# DIOT_Connectors.net
KiCad netlist of a schematic drawn in Altium Designer
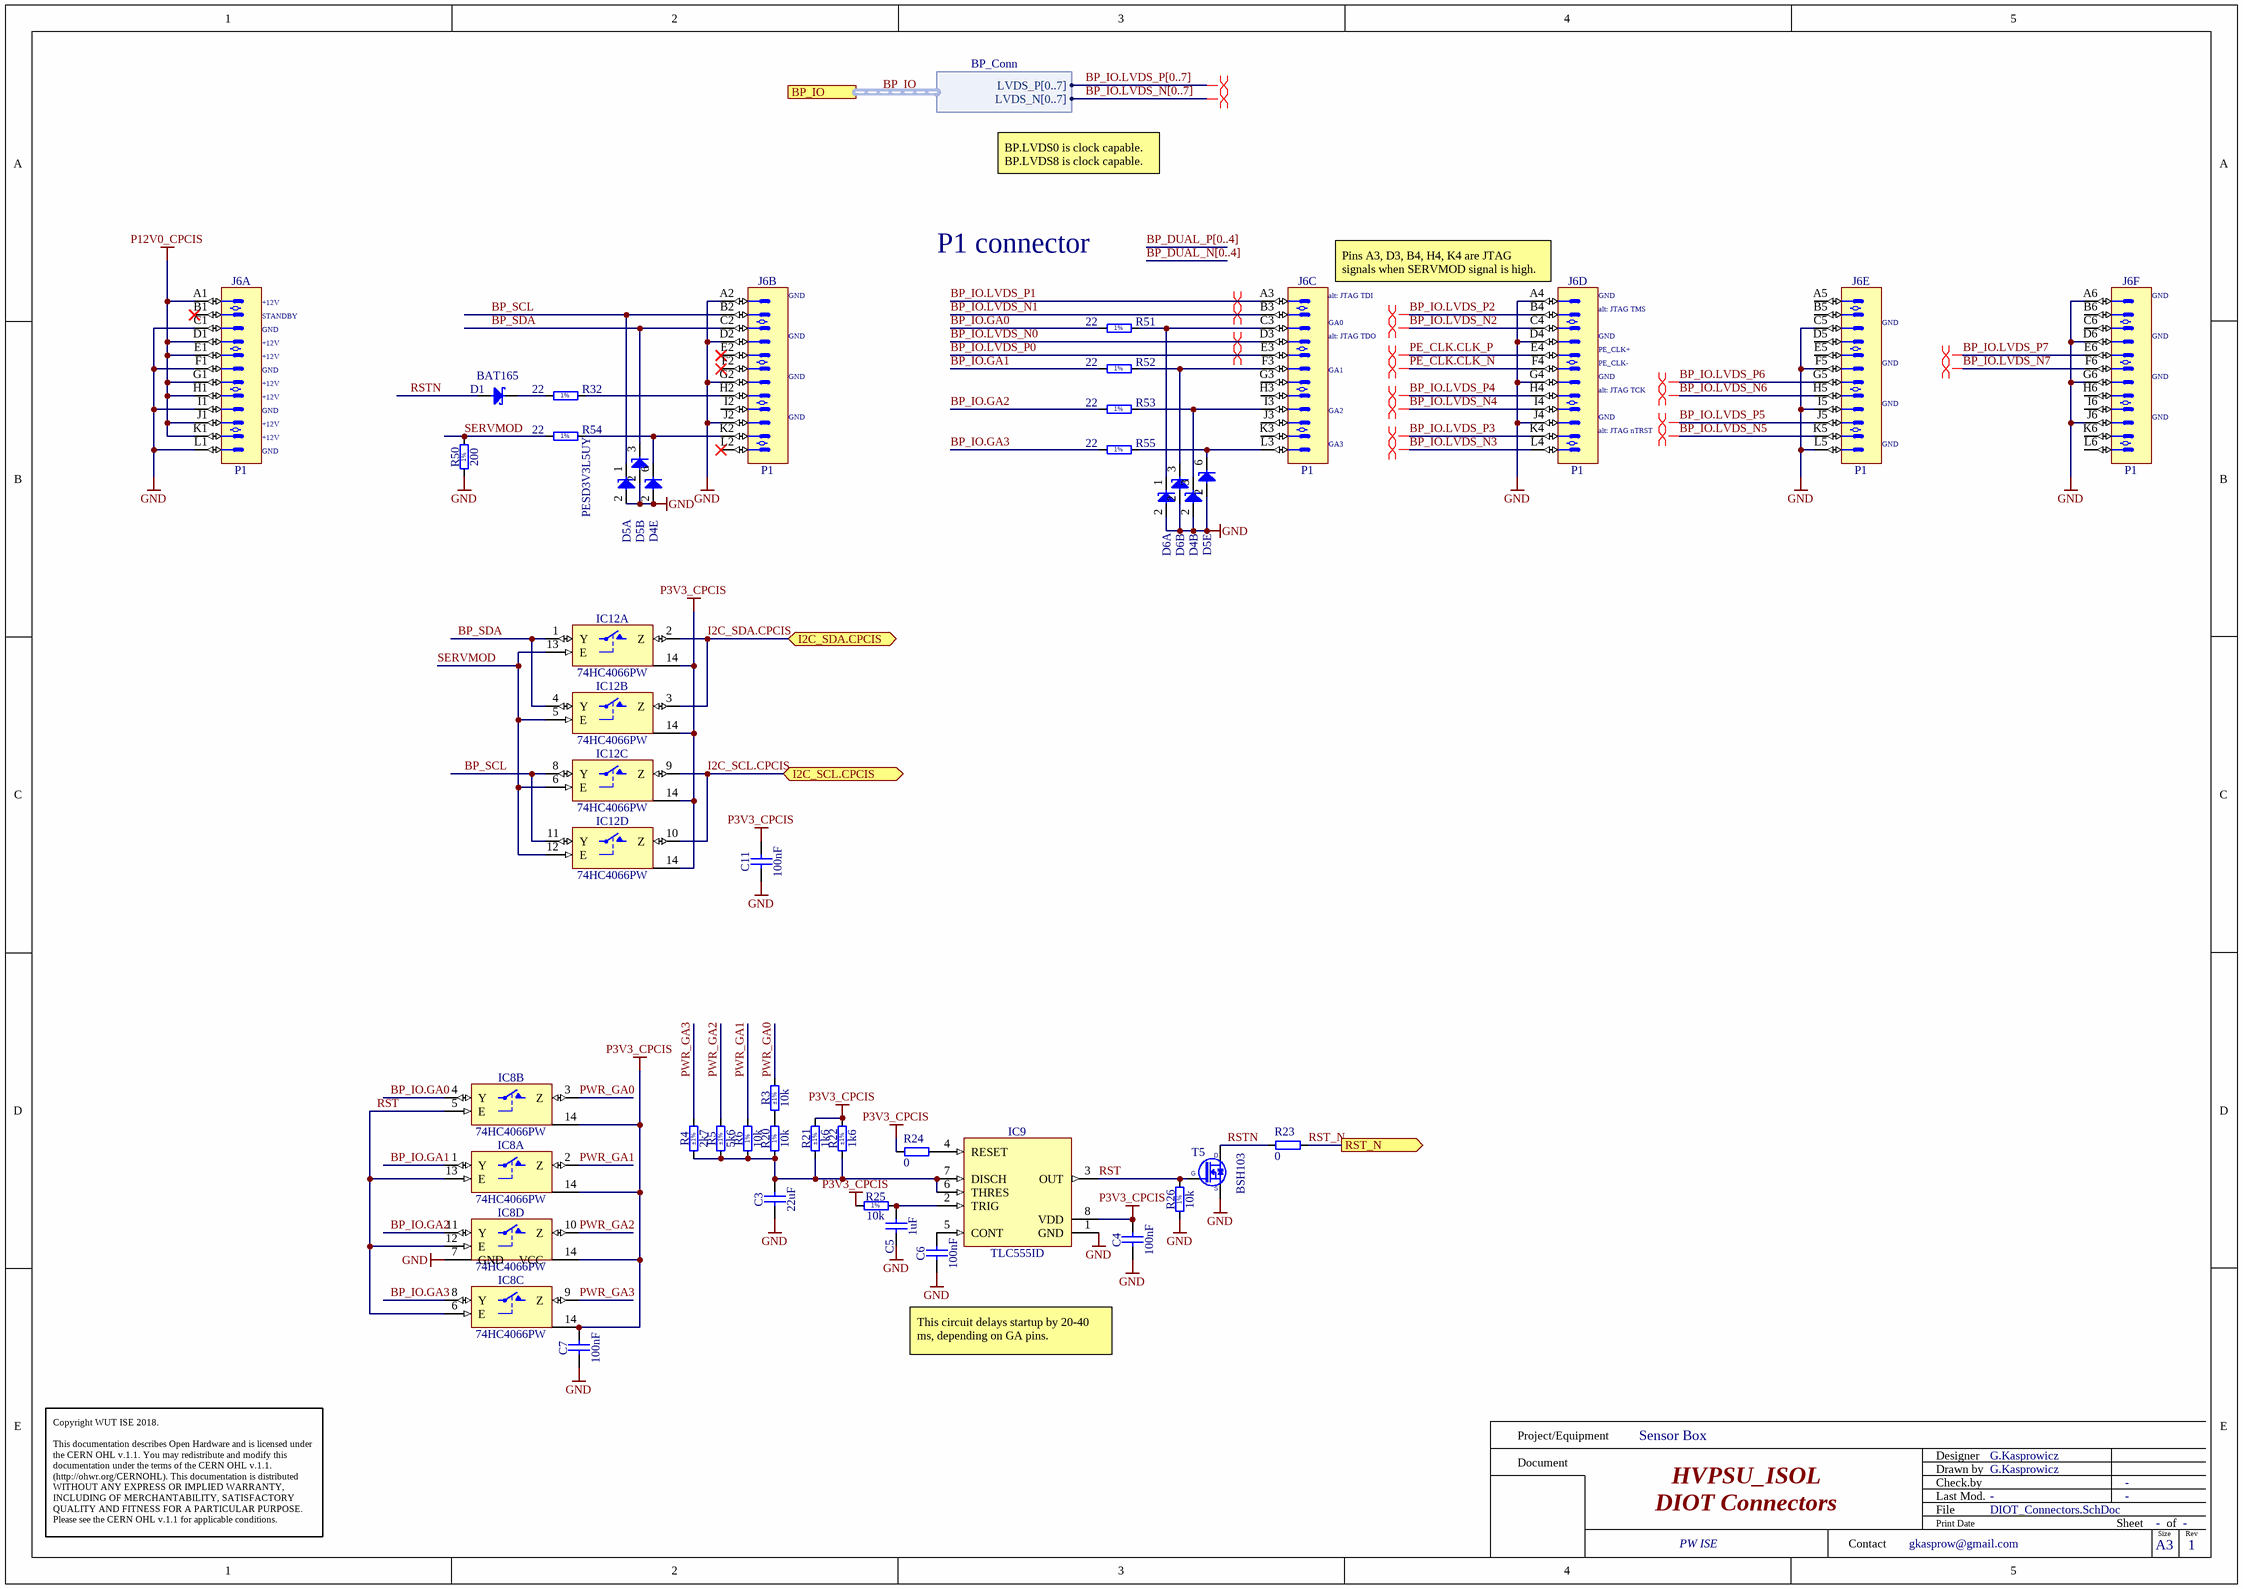
[diagram p0: DIOT_Connectors.SchDoc]

(export (version "E")
  (design (tool "Eeschema 10.0.6"))
  (components
    (comp (ref "C3")
      (value "22uF")
      (footprint "CAPC1608X90N")
      (description "Non-polarised capacitor")
      (fields
        (field (name "MANUFACTURER") "GENERIC")
        (field (name "PART NUMBER") "CC0603_22UF_6.3V_20%_X5R")
        (field (name "AUTHOR") "CERN DEM JLC")
      )
      (libsource (lib "Capacitors") (part "Capacitor - non polarized"))
    )
    (comp (ref "C4")
      (value "100nF")
      (footprint "CAPC1005X55N")
      (description "Non-polarised capacitor")
      (fields
        (field (name "PART NUMBER") "CC0402_100NF_16V_10%_X5R")
        (field (name "VOLTAGE") "16V")
        (field (name "AUTHOR") "CERN DEM JLC")
      )
      (libsource (lib "Capacitors") (part "Capacitor - non polarized"))
    )
    (comp (ref "C5")
      (value "1uF")
      (footprint "CAPC1005X55N")
      (description "Non-polarised capacitor")
      (fields
        (field (name "PART NUMBER") "CC0402_1UF_16V_10%_X5R")
        (field (name "VOLTAGE") "16V")
        (field (name "AUTHOR") "CERN DEM JLC")
      )
      (libsource (lib "Capacitors") (part "Capacitor - non polarized"))
    )
    (comp (ref "C6")
      (value "100nF")
      (footprint "CAPC1005X55N")
      (description "Non-polarised capacitor")
      (fields
        (field (name "PART NUMBER") "CC0402_100NF_16V_10%_X5R")
        (field (name "VOLTAGE") "16V")
        (field (name "AUTHOR") "CERN DEM JLC")
      )
      (libsource (lib "Capacitors") (part "Capacitor - non polarized"))
    )
    (comp (ref "C7")
      (value "100nF")
      (footprint "CAPC1005X55N")
      (description "Non-polarised capacitor")
      (fields
        (field (name "PART NUMBER") "CC0402_100NF_16V_10%_X5R")
        (field (name "VOLTAGE") "16V")
        (field (name "AUTHOR") "CERN DEM JLC")
      )
      (libsource (lib "Capacitors") (part "Capacitor - non polarized"))
    )
    (comp (ref "C11")
      (value "100nF")
      (footprint "CAPC1005X55N")
      (description "Non-polarised capacitor")
      (fields
        (field (name "PART NUMBER") "CC0402_100NF_16V_10%_X5R")
        (field (name "VOLTAGE") "16V")
        (field (name "AUTHOR") "CERN DEM JLC")
      )
      (libsource (lib "Capacitors") (part "Capacitor - non polarized"))
    )
    (comp (ref "D1")
      (value "BAT165")
      (footprint "SOD2512X110N")
      (description "Schottky Diode")
      (fields
        (field (name "MANUFACTURER") "INFINEON")
        (field (name "VOLTAGE") "40V")
        (field (name "AUTHOR") "CERN DEM JLC")
      )
      (libsource (lib "ICs And Semiconductors") (part "Diode Schottky"))
    )
    (comp (ref "D4")
      (value "PESD3V3L5UY")
      (footprint "SOT65P210X110-6N")
      (description "Fivefold ESD Protection Diode Arrays")
      (fields
        (field (name "VOLTAGE") "3.3V")
        (field (name "POWER") "200W")
        (field (name "AUTHOR") "CERN DEM WB")
      )
      (libsource (lib "ICs And Semiconductors") (part "PESD Array 5diodes 6pins Common anode2"))
    )
    (comp (ref "D5")
      (value "PESD3V3L5UY")
      (footprint "SOT65P210X110-6N")
      (description "Fivefold ESD Protection Diode Arrays")
      (fields
        (field (name "VOLTAGE") "3.3V")
        (field (name "POWER") "200W")
        (field (name "AUTHOR") "CERN DEM WB")
      )
      (libsource (lib "ICs And Semiconductors") (part "PESD Array 5diodes 6pins Common anode2"))
    )
    (comp (ref "D6")
      (value "PESD3V3L5UY")
      (footprint "SOT65P210X110-6N")
      (description "Fivefold ESD Protection Diode Arrays")
      (fields
        (field (name "VOLTAGE") "3.3V")
        (field (name "POWER") "200W")
        (field (name "AUTHOR") "CERN DEM WB")
      )
      (libsource (lib "ICs And Semiconductors") (part "PESD Array 5diodes 6pins Common anode2"))
    )
    (comp (ref "IC8")
      (value "74HC4066PW")
      (footprint "SOP65P640X110-14N")
      (fields (field (name "MANUFACTURER") "NXP SEMICONDUCTORS") (field (name "AUTHOR") "CERN DEM JLC"))
      (libsource (lib "ICs And Semiconductors") (part "4066"))
    )
    (comp (ref "IC9")
      (value "TLC555ID")
      (footprint "SOIC127P600X175-8N")
      (description "LinCMOS Timer")
      (fields (field (name "MANUFACTURER") "TEXAS INSTRUMENTS") (field (name "AUTHOR") "CERN DEM JMW"))
      (libsource (lib "ICs And Semiconductors") (part "TLC555"))
    )
    (comp (ref "IC12")
      (value "74HC4066PW")
      (footprint "SOP65P640X110-14N")
      (fields (field (name "MANUFACTURER") "NXP SEMICONDUCTORS") (field (name "AUTHOR") "CERN DEM JLC"))
      (libsource (lib "ICs And Semiconductors") (part "4066"))
    )
    (comp (ref "J6")
      (value "P1")
      (footprint "AMPHENOL_10052825-101LF")
      (description "72 Contacts Header, 6 Columns, 4 Pairs per Column")
      (fields
        (field (name "PART NUMBER") "AMPHENOL_10052825-101LF")
        (field (name "MANUFACTURER") "AMPHENOL")
        (field (name "AUTHOR") "CERN DEM MR")
      )
      (libsource (lib "Connectors") (part "AMPHENOL_10052825-101LF"))
    )
    (comp (ref "R3")
      (value "10k")
      (footprint "RESC1005X40N")
      (description "Resistor - 1%")
      (fields
        (field (name "PART NUMBER") "R0402_10K_1%_0.0625W_100PPM")
        (field (name "POWER") "0.0625W")
        (field (name "TOLERANCE") "±1%")
        (field (name "AUTHOR") "CERN DEM JLC")
      )
      (libsource (lib "Resistors") (part "Resistor - 1%"))
    )
    (comp (ref "R4")
      (value "2k7")
      (footprint "RESC1608X55N")
      (description "Resistor - 1%")
      (fields
        (field (name "PART NUMBER") "R0603_2K7_1%_0.1W_100PPM")
        (field (name "POWER") "0.1W")
        (field (name "TOLERANCE") "±1%")
        (field (name "AUTHOR") "CERN DEM JLC")
      )
      (libsource (lib "") (part "Resistor - 1%_1"))
    )
    (comp (ref "R5")
      (value "5k6")
      (footprint "RESC1005X40N")
      (description "Resistor - 1%")
      (fields
        (field (name "PART NUMBER") "R0402_5K6_1%_0.0625W_100PPM")
        (field (name "POWER") "0.0625W")
        (field (name "TOLERANCE") "±1%")
        (field (name "AUTHOR") "CERN DEM JLC")
      )
      (libsource (lib "Resistors") (part "Resistor - 1%"))
    )
    (comp (ref "R6")
      (value "10k")
      (footprint "RESC1005X40N")
      (description "Resistor - 1%")
      (fields
        (field (name "PART NUMBER") "R0402_1K_1%_0.0625W_100PPM")
        (field (name "POWER") "0.0625W")
        (field (name "AUTHOR") "CERN DEM JLC")
      )
      (libsource (lib "Resistors") (part "Resistor - 1%"))
    )
    (comp (ref "R20")
      (value "10k")
      (footprint "RESC1005X40N")
      (description "Resistor - 1%")
      (fields
        (field (name "PART NUMBER") "R0402_1K_1%_0.0625W_100PPM")
        (field (name "POWER") "0.0625W")
        (field (name "AUTHOR") "CERN DEM JLC")
      )
      (libsource (lib "Resistors") (part "Resistor - 1%"))
    )
    (comp (ref "R21")
      (value "1k6")
      (footprint "RESC1005X40N")
      (description "Resistor - 1%")
      (fields
        (field (name "PART NUMBER") "R0402_1K6_1%_0.0625W_100PPM")
        (field (name "POWER") "0.0625W")
        (field (name "TOLERANCE") "±1%")
        (field (name "AUTHOR") "CERN DEM JLC")
      )
      (libsource (lib "Resistors") (part "Resistor - 1%"))
    )
    (comp (ref "R22")
      (value "1k6")
      (footprint "RESC1005X40N")
      (description "Resistor - 1%")
      (fields
        (field (name "PART NUMBER") "R0402_1K6_1%_0.0625W_100PPM")
        (field (name "POWER") "0.0625W")
        (field (name "TOLERANCE") "±1%")
        (field (name "AUTHOR") "CERN DEM JLC")
      )
      (libsource (lib "Resistors") (part "Resistor - 1%"))
    )
    (comp (ref "R23")
      (value "0")
      (footprint "RESC1005X40N")
      (description "Resistor")
      (fields
        (field (name "PART NUMBER") "R0402_0R_JUMPER")
        (field (name "MANUFACTURER") "GENERIC")
        (field (name "AUTHOR") "CERN DEM JLC")
      )
      (libsource (lib "Resistors") (part "Resistor"))
    )
    (comp (ref "R24")
      (value "0")
      (footprint "RESC1005X40N")
      (description "Resistor")
      (fields
        (field (name "PART NUMBER") "R0402_0R_JUMPER")
        (field (name "MANUFACTURER") "GENERIC")
        (field (name "AUTHOR") "CERN DEM JLC")
      )
      (libsource (lib "Resistors") (part "Resistor"))
    )
    (comp (ref "R25")
      (value "10k")
      (footprint "RESC1005X40N")
      (description "Resistor - 1%")
      (fields
        (field (name "PART NUMBER") "R0402_10K_1%_0.0625W_100PPM")
        (field (name "POWER") "0.0625W")
        (field (name "AUTHOR") "CERN DEM JLC")
      )
      (libsource (lib "Resistors") (part "Resistor - 1%"))
    )
    (comp (ref "R26")
      (value "10k")
      (footprint "RESC1005X40N")
      (description "Resistor - 1%")
      (fields
        (field (name "PART NUMBER") "R0402_10K_1%_0.0625W_100PPM")
        (field (name "POWER") "0.0625W")
        (field (name "AUTHOR") "CERN DEM JLC")
      )
      (libsource (lib "Resistors") (part "Resistor - 1%"))
    )
    (comp (ref "R32")
      (value "22")
      (footprint "RESC1005X40N")
      (description "Resistor - 1%")
      (fields
        (field (name "PART NUMBER") "R0402_22R_1%_0.0625W_100PPM")
        (field (name "POWER") "0.0625W")
        (field (name "AUTHOR") "CERN DEM JLC")
      )
      (libsource (lib "Resistors") (part "Resistor - 1%"))
    )
    (comp (ref "R50")
      (value "200")
      (footprint "RESC1005X40N")
      (description "Resistor - 1%")
      (fields
        (field (name "PART NUMBER") "R0402_200R_1%_0.0625W_100PPM")
        (field (name "POWER") "0.0625W")
        (field (name "AUTHOR") "CERN DEM JLC")
      )
      (libsource (lib "Resistors") (part "Resistor - 1%"))
    )
    (comp (ref "R51")
      (value "22")
      (footprint "RESC1005X40N")
      (description "Resistor - 1%")
      (fields
        (field (name "PART NUMBER") "R0402_22R_1%_0.0625W_100PPM")
        (field (name "POWER") "0.0625W")
        (field (name "AUTHOR") "CERN DEM JLC")
      )
      (libsource (lib "Resistors") (part "Resistor - 1%"))
    )
    (comp (ref "R52")
      (value "22")
      (footprint "RESC1005X40N")
      (description "Resistor - 1%")
      (fields
        (field (name "PART NUMBER") "R0402_22R_1%_0.0625W_100PPM")
        (field (name "POWER") "0.0625W")
        (field (name "AUTHOR") "CERN DEM JLC")
      )
      (libsource (lib "Resistors") (part "Resistor - 1%"))
    )
    (comp (ref "R53")
      (value "22")
      (footprint "RESC1005X40N")
      (description "Resistor - 1%")
      (fields
        (field (name "PART NUMBER") "R0402_22R_1%_0.0625W_100PPM")
        (field (name "POWER") "0.0625W")
        (field (name "AUTHOR") "CERN DEM JLC")
      )
      (libsource (lib "Resistors") (part "Resistor - 1%"))
    )
    (comp (ref "R54")
      (value "22")
      (footprint "RESC1005X40N")
      (description "Resistor - 1%")
      (fields
        (field (name "PART NUMBER") "R0402_22R_1%_0.0625W_100PPM")
        (field (name "POWER") "0.0625W")
        (field (name "AUTHOR") "CERN DEM JLC")
      )
      (libsource (lib "Resistors") (part "Resistor - 1%"))
    )
    (comp (ref "R55")
      (value "22")
      (footprint "RESC1005X40N")
      (description "Resistor - 1%")
      (fields
        (field (name "PART NUMBER") "R0402_22R_1%_0.0625W_100PPM")
        (field (name "POWER") "0.0625W")
        (field (name "AUTHOR") "CERN DEM JLC")
      )
      (libsource (lib "Resistors") (part "Resistor - 1%"))
    )
    (comp (ref "T5")
      (value "BSH103")
      (footprint "SOT95P230X110-3N")
      (description "N-CHANNEL MOSFET WITH DIODE")
      (fields (field (name "MANUFACTURER") "NEXPERIA") (field (name "AUTHOR") "CERN DEM JLC"))
      (libsource (lib "ICs And Semiconductors") (part "N-MOSFET-D 1G 2S 3D"))
    )
  )
  (nets
    (net (code "14") (name "/BP_IO.GA0") (class "Default")
      (node (ref "IC8") (pin "4") (pinfunction "Y_4") (pintype "bidirectional"))
      (node (ref "R51") (pin "1") (pinfunction "1_1") (pintype "passive"))
    )
    (net (code "15") (name "/BP_IO.GA1") (class "Default")
      (node (ref "IC8") (pin "1") (pinfunction "Y_1") (pintype "bidirectional"))
      (node (ref "R52") (pin "1") (pinfunction "1_1") (pintype "passive"))
    )
    (net (code "16") (name "/BP_IO.GA2") (class "Default")
      (node (ref "IC8") (pin "11") (pinfunction "Y_11") (pintype "bidirectional"))
      (node (ref "R53") (pin "1") (pinfunction "1_1") (pintype "passive"))
    )
    (net (code "17") (name "/BP_IO.GA3") (class "Default")
      (node (ref "IC8") (pin "8") (pinfunction "Y_8") (pintype "bidirectional"))
      (node (ref "R55") (pin "1") (pinfunction "1_1") (pintype "passive"))
    )
    (net (code "18") (name "/BP_IO.LVDS_N0") (class "Default")
      (node (ref "J6") (pin "D3") (pinfunction "D3_D3") (pintype "bidirectional"))
    )
    (net (code "19") (name "/BP_IO.LVDS_N1") (class "Default")
      (node (ref "J6") (pin "B3") (pinfunction "B3_B3") (pintype "bidirectional"))
    )
    (net (code "20") (name "/BP_IO.LVDS_N2") (class "Default")
      (node (ref "J6") (pin "C4") (pinfunction "C4_C4") (pintype "bidirectional"))
    )
    (net (code "21") (name "/BP_IO.LVDS_N3") (class "Default")
      (node (ref "J6") (pin "L4") (pinfunction "L4_L4") (pintype "bidirectional"))
    )
    (net (code "22") (name "/BP_IO.LVDS_N4") (class "Default")
      (node (ref "J6") (pin "I4") (pinfunction "I4_I4") (pintype "bidirectional"))
    )
    (net (code "23") (name "/BP_IO.LVDS_N5") (class "Default")
      (node (ref "J6") (pin "K5") (pinfunction "K5_K5") (pintype "bidirectional"))
    )
    (net (code "24") (name "/BP_IO.LVDS_N6") (class "Default")
      (node (ref "J6") (pin "H5") (pinfunction "H5_H5") (pintype "bidirectional"))
    )
    (net (code "25") (name "/BP_IO.LVDS_N7") (class "Default")
      (node (ref "J6") (pin "F6") (pinfunction "F6_F6") (pintype "bidirectional"))
    )
    (net (code "27") (name "/BP_IO.LVDS_P0") (class "Default")
      (node (ref "J6") (pin "E3") (pinfunction "E3_E3") (pintype "bidirectional"))
    )
    (net (code "28") (name "/BP_IO.LVDS_P1") (class "Default")
      (node (ref "J6") (pin "A3") (pinfunction "A3_A3") (pintype "bidirectional"))
    )
    (net (code "29") (name "/BP_IO.LVDS_P2") (class "Default")
      (node (ref "J6") (pin "B4") (pinfunction "B4_B4") (pintype "bidirectional"))
    )
    (net (code "30") (name "/BP_IO.LVDS_P3") (class "Default")
      (node (ref "J6") (pin "K4") (pinfunction "K4_K4") (pintype "bidirectional"))
    )
    (net (code "31") (name "/BP_IO.LVDS_P4") (class "Default")
      (node (ref "J6") (pin "H4") (pinfunction "H4_H4") (pintype "bidirectional"))
    )
    (net (code "32") (name "/BP_IO.LVDS_P5") (class "Default")
      (node (ref "J6") (pin "J5") (pinfunction "J5_J5") (pintype "bidirectional"))
    )
    (net (code "33") (name "/BP_IO.LVDS_P6") (class "Default")
      (node (ref "J6") (pin "G5") (pinfunction "G5_G5") (pintype "bidirectional"))
    )
    (net (code "34") (name "/BP_IO.LVDS_P7") (class "Default")
      (node (ref "J6") (pin "E6") (pinfunction "E6_E6") (pintype "bidirectional"))
    )
    (net (code "37") (name "/BP_SCL") (class "Default")
      (node (ref "D5") (pin "1") (pinfunction "C_1") (pintype "passive"))
      (node (ref "IC12") (pin "11") (pinfunction "Y_11") (pintype "bidirectional"))
      (node (ref "IC12") (pin "8") (pinfunction "Y_8") (pintype "bidirectional"))
      (node (ref "J6") (pin "B2") (pinfunction "B2_B2") (pintype "bidirectional"))
    )
    (net (code "38") (name "/BP_SDA") (class "Default")
      (node (ref "D5") (pin "3") (pinfunction "C_3") (pintype "passive"))
      (node (ref "IC12") (pin "1") (pinfunction "Y_1") (pintype "bidirectional"))
      (node (ref "IC12") (pin "4") (pinfunction "Y_4") (pintype "bidirectional"))
      (node (ref "J6") (pin "C2") (pinfunction "C2_C2") (pintype "bidirectional"))
    )
    (net (code "39") (name "/I2C_SCL.CPCIS") (class "Default")
      (node (ref "IC12") (pin "10") (pinfunction "Z_10") (pintype "bidirectional"))
      (node (ref "IC12") (pin "9") (pinfunction "Z_9") (pintype "bidirectional"))
    )
    (net (code "40") (name "/I2C_SDA.CPCIS") (class "Default")
      (node (ref "IC12") (pin "2") (pinfunction "Z_2") (pintype "bidirectional"))
      (node (ref "IC12") (pin "3") (pinfunction "Z_3") (pintype "bidirectional"))
    )
    (net (code "41") (name "/PE_CLK.CLK_N") (class "Default")
      (node (ref "J6") (pin "F4") (pinfunction "F4_F4") (pintype "bidirectional"))
    )
    (net (code "42") (name "/PE_CLK.CLK_P") (class "Default")
      (node (ref "J6") (pin "E4") (pinfunction "E4_E4") (pintype "bidirectional"))
    )
    (net (code "43") (name "/PWR_GA0") (class "Default")
      (node (ref "IC8") (pin "3") (pinfunction "Z_3") (pintype "bidirectional"))
      (node (ref "R3") (pin "2") (pinfunction "2_2") (pintype "passive"))
    )
    (net (code "44") (name "/PWR_GA1") (class "Default")
      (node (ref "IC8") (pin "2") (pinfunction "Z_2") (pintype "bidirectional"))
      (node (ref "R6") (pin "2") (pinfunction "2_2") (pintype "passive"))
    )
    (net (code "45") (name "/PWR_GA2") (class "Default")
      (node (ref "IC8") (pin "10") (pinfunction "Z_10") (pintype "bidirectional"))
      (node (ref "R5") (pin "2") (pinfunction "2_2") (pintype "passive"))
    )
    (net (code "46") (name "/PWR_GA3") (class "Default")
      (node (ref "IC8") (pin "9") (pinfunction "Z_9") (pintype "bidirectional"))
      (node (ref "R4") (pin "2") (pinfunction "2_2") (pintype "passive"))
    )
    (net (code "47") (name "/RST") (class "Default")
      (node (ref "IC8") (pin "12") (pinfunction "E_12") (pintype "input"))
      (node (ref "IC8") (pin "13") (pinfunction "E_13") (pintype "input"))
      (node (ref "IC8") (pin "5") (pinfunction "E_5") (pintype "input"))
      (node (ref "IC8") (pin "6") (pinfunction "E_6") (pintype "input"))
      (node (ref "IC9") (pin "3") (pinfunction "OUT_3") (pintype "output"))
      (node (ref "R26") (pin "2") (pinfunction "2_2") (pintype "passive"))
      (node (ref "T5") (pin "1") (pinfunction "G_1") (pintype "passive"))
    )
    (net (code "48") (name "/RSTN") (class "Default")
      (node (ref "D1") (pin "2") (pinfunction "A_2") (pintype "passive"))
      (node (ref "R23") (pin "2") (pinfunction "2_2") (pintype "passive"))
      (node (ref "T5") (pin "3") (pinfunction "D_3") (pintype "passive"))
    )
    (net (code "49") (name "/RST_N") (class "Default")
      (node (ref "R23") (pin "1") (pinfunction "1_1") (pintype "passive"))
    )
    (net (code "50") (name "/SERVMOD") (class "Default")
      (node (ref "IC12") (pin "12") (pinfunction "E_12") (pintype "input"))
      (node (ref "IC12") (pin "13") (pinfunction "E_13") (pintype "input"))
      (node (ref "IC12") (pin "5") (pinfunction "E_5") (pintype "input"))
      (node (ref "IC12") (pin "6") (pinfunction "E_6") (pintype "input"))
      (node (ref "R50") (pin "2") (pinfunction "2_2") (pintype "passive"))
      (node (ref "R54") (pin "1") (pinfunction "1_1") (pintype "passive"))
    )
    (net (code "51") (name "GND") (class "Default")
      (node (ref "C11") (pin "1") (pinfunction "1_1") (pintype "passive"))
      (node (ref "C3") (pin "1") (pinfunction "1_1") (pintype "passive"))
      (node (ref "C4") (pin "1") (pinfunction "1_1") (pintype "passive"))
      (node (ref "C5") (pin "1") (pinfunction "1_1") (pintype "passive"))
      (node (ref "C6") (pin "1") (pinfunction "1_1") (pintype "passive"))
      (node (ref "C7") (pin "1") (pinfunction "1_1") (pintype "passive"))
      (node (ref "D4") (pin "2") (pinfunction "A_2") (pintype "passive"))
      (node (ref "D5") (pin "2") (pinfunction "A_2") (pintype "passive"))
      (node (ref "D6") (pin "2") (pinfunction "A_2") (pintype "passive"))
      (node (ref "IC12") (pin "7") (pinfunction "GND_7") (pintype "power_in"))
      (node (ref "IC8") (pin "7") (pinfunction "GND_7") (pintype "power_in"))
      (node (ref "IC9") (pin "1") (pinfunction "GND_1") (pintype "power_in"))
      (node (ref "J6") (pin "A2") (pinfunction "A2_A2") (pintype "bidirectional"))
      (node (ref "J6") (pin "A4") (pinfunction "A4_A4") (pintype "bidirectional"))
      (node (ref "J6") (pin "A6") (pinfunction "A6_A6") (pintype "bidirectional"))
      (node (ref "J6") (pin "C1") (pinfunction "C1_C1") (pintype "bidirectional"))
      (node (ref "J6") (pin "C5") (pinfunction "C5_C5") (pintype "bidirectional"))
      (node (ref "J6") (pin "D2") (pinfunction "D2_D2") (pintype "bidirectional"))
      (node (ref "J6") (pin "D4") (pinfunction "D4_D4") (pintype "bidirectional"))
      (node (ref "J6") (pin "D6") (pinfunction "D6_D6") (pintype "bidirectional"))
      (node (ref "J6") (pin "F1") (pinfunction "F1_F1") (pintype "bidirectional"))
      (node (ref "J6") (pin "F5") (pinfunction "F5_F5") (pintype "bidirectional"))
      (node (ref "J6") (pin "G2") (pinfunction "G2_G2") (pintype "bidirectional"))
      (node (ref "J6") (pin "G4") (pinfunction "G4_G4") (pintype "bidirectional"))
      (node (ref "J6") (pin "G6") (pinfunction "G6_G6") (pintype "bidirectional"))
      (node (ref "J6") (pin "I1") (pinfunction "I1_I1") (pintype "bidirectional"))
      (node (ref "J6") (pin "I5") (pinfunction "I5_I5") (pintype "bidirectional"))
      (node (ref "J6") (pin "J2") (pinfunction "J2_J2") (pintype "bidirectional"))
      (node (ref "J6") (pin "J4") (pinfunction "J4_J4") (pintype "bidirectional"))
      (node (ref "J6") (pin "J6") (pinfunction "J6_J6") (pintype "bidirectional"))
      (node (ref "J6") (pin "L1") (pinfunction "L1_L1") (pintype "bidirectional"))
      (node (ref "J6") (pin "L5") (pinfunction "L5_L5") (pintype "bidirectional"))
      (node (ref "R26") (pin "1") (pinfunction "1_1") (pintype "passive"))
      (node (ref "R50") (pin "1") (pinfunction "1_1") (pintype "passive"))
      (node (ref "T5") (pin "2") (pinfunction "S_2") (pintype "passive"))
    )
    (net (code "52") (name "Net-(D1-C)") (class "Default")
      (node (ref "D1") (pin "1") (pinfunction "C_1") (pintype "passive"))
      (node (ref "R32") (pin "1") (pinfunction "1_1") (pintype "passive"))
    )
    (net (code "53") (name "Net-(D4B-C)") (class "Default")
      (node (ref "D4") (pin "3") (pinfunction "C_3") (pintype "passive"))
      (node (ref "J6") (pin "I3") (pinfunction "I3_I3") (pintype "bidirectional"))
      (node (ref "R53") (pin "2") (pinfunction "2_2") (pintype "passive"))
    )
    (net (code "54") (name "Net-(D4E-C)") (class "Default")
      (node (ref "D4") (pin "6") (pinfunction "C_6") (pintype "passive"))
      (node (ref "J6") (pin "K2") (pinfunction "K2_K2") (pintype "bidirectional"))
      (node (ref "R54") (pin "2") (pinfunction "2_2") (pintype "passive"))
    )
    (net (code "55") (name "Net-(D5E-C)") (class "Default")
      (node (ref "D5") (pin "6") (pinfunction "C_6") (pintype "passive"))
      (node (ref "J6") (pin "L3") (pinfunction "L3_L3") (pintype "bidirectional"))
      (node (ref "R55") (pin "2") (pinfunction "2_2") (pintype "passive"))
    )
    (net (code "56") (name "Net-(D6A-C)") (class "Default")
      (node (ref "D6") (pin "1") (pinfunction "C_1") (pintype "passive"))
      (node (ref "J6") (pin "C3") (pinfunction "C3_C3") (pintype "bidirectional"))
      (node (ref "R51") (pin "2") (pinfunction "2_2") (pintype "passive"))
    )
    (net (code "57") (name "Net-(D6B-C)") (class "Default")
      (node (ref "D6") (pin "3") (pinfunction "C_3") (pintype "passive"))
      (node (ref "J6") (pin "F3") (pinfunction "F3_F3") (pintype "bidirectional"))
      (node (ref "R52") (pin "2") (pinfunction "2_2") (pintype "passive"))
    )
    (net (code "58") (name "Net-(IC9-CONT)") (class "Default")
      (node (ref "C6") (pin "2") (pinfunction "2_2") (pintype "passive"))
      (node (ref "IC9") (pin "5") (pinfunction "CONT_5") (pintype "input"))
    )
    (net (code "59") (name "Net-(IC9-DISCH)") (class "Default")
      (node (ref "C3") (pin "2") (pinfunction "2_2") (pintype "passive"))
      (node (ref "IC9") (pin "6") (pinfunction "THRES_6") (pintype "input"))
      (node (ref "IC9") (pin "7") (pinfunction "DISCH_7") (pintype "input"))
      (node (ref "R20") (pin "1") (pinfunction "1_1") (pintype "passive"))
      (node (ref "R21") (pin "1") (pinfunction "1_1") (pintype "passive"))
      (node (ref "R22") (pin "1") (pinfunction "1_1") (pintype "passive"))
      (node (ref "R4") (pin "1") (pinfunction "1_1") (pintype "passive"))
      (node (ref "R5") (pin "1") (pinfunction "1_1") (pintype "passive"))
      (node (ref "R6") (pin "1") (pinfunction "1_1") (pintype "passive"))
    )
    (net (code "60") (name "Net-(IC9-RESET)") (class "Default")
      (node (ref "IC9") (pin "4") (pinfunction "RESET_4") (pintype "input"))
      (node (ref "R24") (pin "1") (pinfunction "1_1") (pintype "passive"))
    )
    (net (code "61") (name "Net-(IC9-TRIG)") (class "Default")
      (node (ref "C5") (pin "2") (pinfunction "2_2") (pintype "passive"))
      (node (ref "IC9") (pin "2") (pinfunction "TRIG_2") (pintype "input"))
      (node (ref "R25") (pin "2") (pinfunction "2_2") (pintype "passive"))
    )
    (net (code "62") (name "Net-(J6-PadH2)") (class "Default")
      (node (ref "J6") (pin "H2") (pinfunction "H2_H2") (pintype "bidirectional"))
      (node (ref "R32") (pin "2") (pinfunction "2_2") (pintype "passive"))
    )
    (net (code "63") (name "Net-(R20-Pad2)") (class "Default")
      (node (ref "R20") (pin "2") (pinfunction "2_2") (pintype "passive"))
      (node (ref "R3") (pin "1") (pinfunction "1_1") (pintype "passive"))
    )
    (net (code "64") (name "P3V3_CPCIS") (class "Default")
      (node (ref "C11") (pin "2") (pinfunction "2_2") (pintype "passive"))
      (node (ref "C4") (pin "2") (pinfunction "2_2") (pintype "passive"))
      (node (ref "C7") (pin "2") (pinfunction "2_2") (pintype "passive"))
      (node (ref "IC12") (pin "14") (pinfunction "VCC_14") (pintype "power_in"))
      (node (ref "IC8") (pin "14") (pinfunction "VCC_14") (pintype "power_in"))
      (node (ref "IC9") (pin "8") (pinfunction "VDD_8") (pintype "power_in"))
      (node (ref "R21") (pin "2") (pinfunction "2_2") (pintype "passive"))
      (node (ref "R22") (pin "2") (pinfunction "2_2") (pintype "passive"))
      (node (ref "R24") (pin "2") (pinfunction "2_2") (pintype "passive"))
      (node (ref "R25") (pin "1") (pinfunction "1_1") (pintype "passive"))
    )
    (net (code "65") (name "P12V0_CPCIS") (class "Default")
      (node (ref "J6") (pin "A1") (pinfunction "A1_A1") (pintype "bidirectional"))
      (node (ref "J6") (pin "D1") (pinfunction "D1_D1") (pintype "bidirectional"))
      (node (ref "J6") (pin "E1") (pinfunction "E1_E1") (pintype "bidirectional"))
      (node (ref "J6") (pin "G1") (pinfunction "G1_G1") (pintype "bidirectional"))
      (node (ref "J6") (pin "H1") (pinfunction "H1_H1") (pintype "bidirectional"))
      (node (ref "J6") (pin "J1") (pinfunction "J1_J1") (pintype "bidirectional"))
      (node (ref "J6") (pin "K1") (pinfunction "K1_K1") (pintype "bidirectional"))
    )
    (net (code "66") (name "unconnected-(J6-PadA5)") (class "Default")
      (node (ref "J6") (pin "A5") (pinfunction "A5_A5") (pintype "bidirectional"))
    )
    (net (code "67") (name "unconnected-(J6-PadB1)") (class "Default")
      (node (ref "J6") (pin "B1") (pinfunction "B1_B1") (pintype "bidirectional+no_connect"))
    )
    (net (code "68") (name "unconnected-(J6-PadB5)") (class "Default")
      (node (ref "J6") (pin "B5") (pinfunction "B5_B5") (pintype "bidirectional"))
    )
    (net (code "69") (name "unconnected-(J6-PadB6)") (class "Default")
      (node (ref "J6") (pin "B6") (pinfunction "B6_B6") (pintype "bidirectional"))
    )
    (net (code "70") (name "unconnected-(J6-PadC6)") (class "Default")
      (node (ref "J6") (pin "C6") (pinfunction "C6_C6") (pintype "bidirectional"))
    )
    (net (code "71") (name "unconnected-(J6-PadD5)") (class "Default")
      (node (ref "J6") (pin "D5") (pinfunction "D5_D5") (pintype "bidirectional"))
    )
    (net (code "72") (name "unconnected-(J6-PadE2)") (class "Default")
      (node (ref "J6") (pin "E2") (pinfunction "E2_E2") (pintype "bidirectional+no_connect"))
    )
    (net (code "73") (name "unconnected-(J6-PadE5)") (class "Default")
      (node (ref "J6") (pin "E5") (pinfunction "E5_E5") (pintype "bidirectional"))
    )
    (net (code "74") (name "unconnected-(J6-PadF2)") (class "Default")
      (node (ref "J6") (pin "F2") (pinfunction "F2_F2") (pintype "bidirectional+no_connect"))
    )
    (net (code "75") (name "unconnected-(J6-PadG3)") (class "Default")
      (node (ref "J6") (pin "G3") (pinfunction "G3_G3") (pintype "bidirectional"))
    )
    (net (code "76") (name "unconnected-(J6-PadH3)") (class "Default")
      (node (ref "J6") (pin "H3") (pinfunction "H3_H3") (pintype "bidirectional"))
    )
    (net (code "77") (name "unconnected-(J6-PadH6)") (class "Default")
      (node (ref "J6") (pin "H6") (pinfunction "H6_H6") (pintype "bidirectional"))
    )
    (net (code "78") (name "unconnected-(J6-PadI2)") (class "Default")
      (node (ref "J6") (pin "I2") (pinfunction "I2_I2") (pintype "bidirectional"))
    )
    (net (code "79") (name "unconnected-(J6-PadI6)") (class "Default")
      (node (ref "J6") (pin "I6") (pinfunction "I6_I6") (pintype "bidirectional"))
    )
    (net (code "80") (name "unconnected-(J6-PadJ3)") (class "Default")
      (node (ref "J6") (pin "J3") (pinfunction "J3_J3") (pintype "bidirectional"))
    )
    (net (code "81") (name "unconnected-(J6-PadK3)") (class "Default")
      (node (ref "J6") (pin "K3") (pinfunction "K3_K3") (pintype "bidirectional"))
    )
    (net (code "82") (name "unconnected-(J6-PadK6)") (class "Default")
      (node (ref "J6") (pin "K6") (pinfunction "K6_K6") (pintype "bidirectional"))
    )
    (net (code "83") (name "unconnected-(J6-PadL2)") (class "Default")
      (node (ref "J6") (pin "L2") (pinfunction "L2_L2") (pintype "bidirectional+no_connect"))
    )
    (net (code "84") (name "unconnected-(J6-PadL6)") (class "Default")
      (node (ref "J6") (pin "L6") (pinfunction "L6_L6") (pintype "bidirectional"))
    )
  )
)
